# XDAmp.net
KiCad netlist of a schematic drawn in Altium Designer
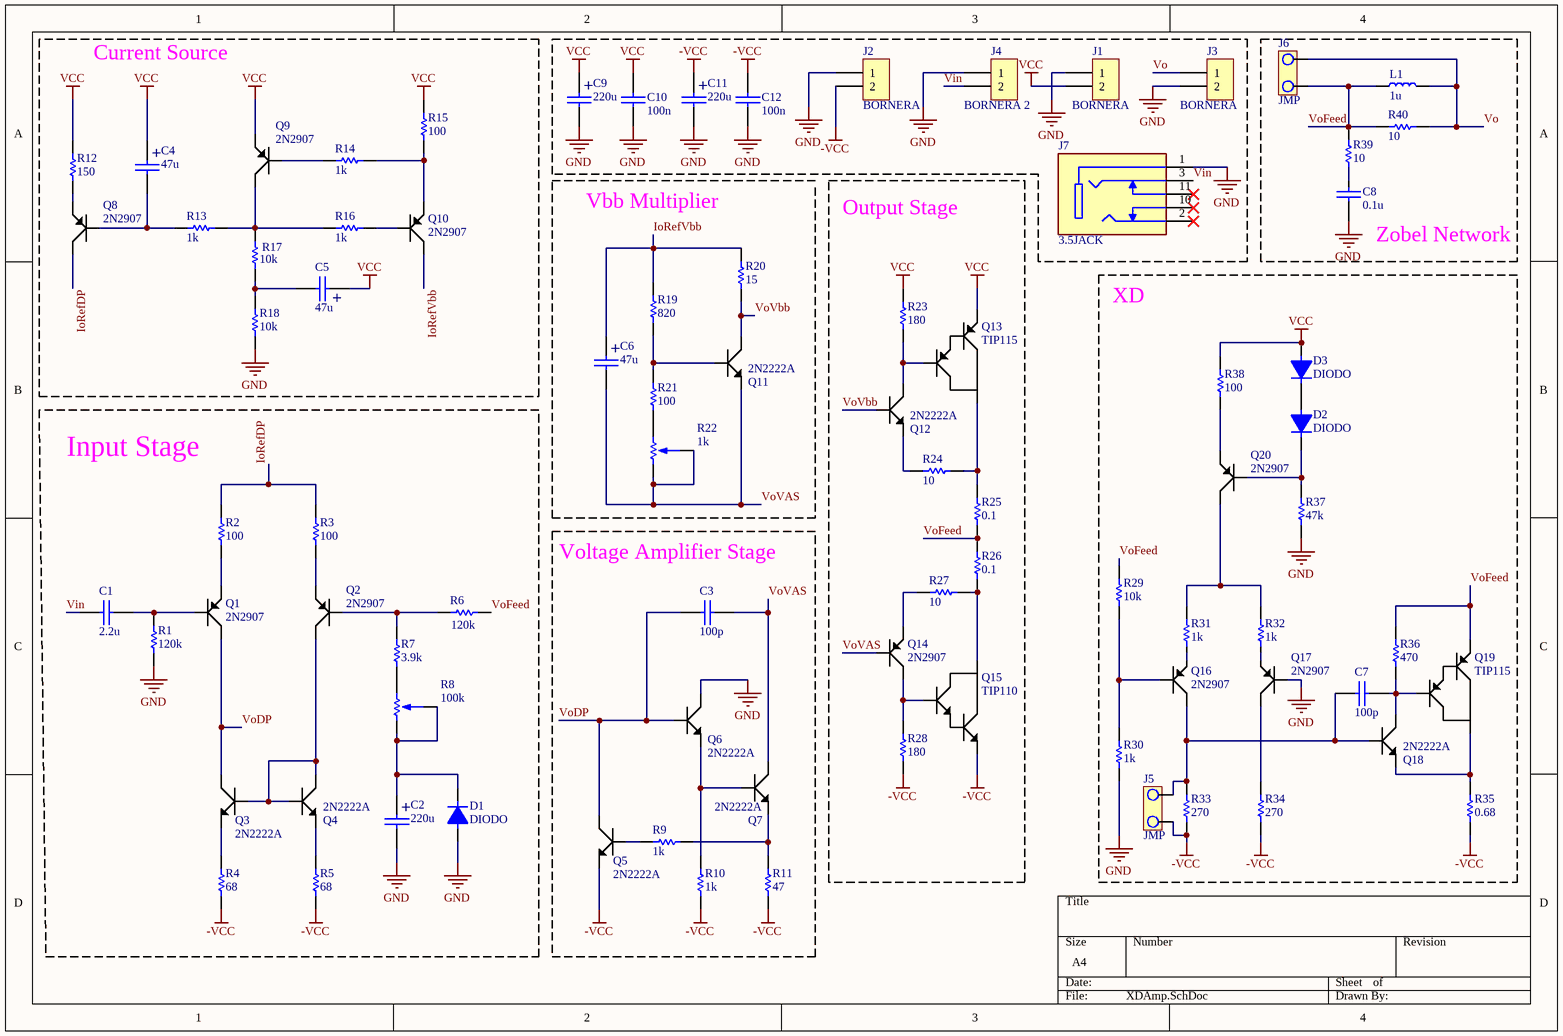
[diagram p0: XDAmp.SchDoc]

(export (version "E")
  (design (tool "Eeschema 10.0.6"))
  (components
    (comp (ref "C1")
      (value "2.2u")
      (footprint "CAP100")
      (description "Capacitor SMD 4.7nF")
      (libsource (lib "XDAmpLib") (part "CAP"))
    )
    (comp (ref "C2") (value "220u") (footprint "CAP300RP") (libsource (lib "XDAmpLib") (part "CAPPOL")))
    (comp (ref "C3")
      (value "100p")
      (footprint "0805CAP")
      (description "Capacitor SMD 4.7nF")
      (libsource (lib "XDAmpLib") (part "CAP"))
    )
    (comp (ref "C4") (value "47u") (footprint "CAP300RP") (libsource (lib "XDAmpLib") (part "CAPPOL")))
    (comp (ref "C5") (value "47u") (footprint "CAP300RP") (libsource (lib "XDAmpLib") (part "CAPPOL")))
    (comp (ref "C6") (value "47u") (footprint "CAP300RP") (libsource (lib "XDAmpLib") (part "CAPPOL")))
    (comp (ref "C7")
      (value "100p")
      (footprint "0805CAP")
      (description "Capacitor SMD 4.7nF")
      (libsource (lib "XDAmpLib") (part "CAP"))
    )
    (comp (ref "C8")
      (value "0.1u")
      (footprint "0805CAP")
      (description "Capacitor SMD 4.7nF")
      (libsource (lib "XDAmpLib") (part "CAP"))
    )
    (comp (ref "C9") (value "220u") (footprint "CAP300RP") (libsource (lib "XDAmpLib") (part "CAPPOL")))
    (comp (ref "C10")
      (value "100n")
      (footprint "0805CAP")
      (description "Capacitor SMD 4.7nF")
      (libsource (lib "XDAmpLib") (part "CAP"))
    )
    (comp (ref "C11") (value "220u") (footprint "CAP300RP") (libsource (lib "XDAmpLib") (part "CAPPOL")))
    (comp (ref "C12")
      (value "100n")
      (footprint "0805CAP")
      (description "Capacitor SMD 4.7nF")
      (libsource (lib "XDAmpLib") (part "CAP"))
    )
    (comp (ref "D1") (value "DIODO") (footprint "DO41") (libsource (lib "XDAmpLib") (part "DIODO")))
    (comp (ref "D2") (value "DIODO") (footprint "DO41") (libsource (lib "XDAmpLib") (part "DIODO")))
    (comp (ref "D3") (value "DIODO") (footprint "DO41") (libsource (lib "XDAmpLib") (part "DIODO")))
    (comp (ref "J1") (value "BORNERA") (footprint "BORNERA2") (libsource (lib "XDAmpLib") (part "BORNERA 2")))
    (comp (ref "J2") (value "BORNERA") (footprint "BORNERA2") (libsource (lib "XDAmpLib") (part "BORNERA 2")))
    (comp (ref "J3") (value "BORNERA") (footprint "BORNERA2") (libsource (lib "XDAmpLib") (part "BORNERA 2")))
    (comp (ref "J4")
      (value "BORNERA 2")
      (footprint "BORNERA2")
      (libsource (lib "XDAmpLib") (part "BORNERA 2"))
    )
    (comp (ref "J5") (value "JMP") (footprint "JUMPER2") (libsource (lib "XDAmpLib") (part "JUMPER")))
    (comp (ref "J6") (value "JMP") (footprint "JUMPER2") (libsource (lib "XDAmpLib") (part "JUMPER")))
    (comp (ref "J7")
      (value "3.5JACK")
      (footprint "3.5JACK")
      (description "3.5 mm Right-Angle Stereo Jack, 5 Pin PCB Mount, Non-Threaded")
      (fields (field (name "MP") "SJ1-3525N"))
      (libsource (lib "XDAmpLib") (part "3.5JACK"))
    )
    (comp (ref "L1") (value "1u") (footprint "RADIALIND") (libsource (lib "XDAmpLib") (part "INDUCTOR_1")))
    (comp (ref "Q1") (value "2N2907") (footprint "TO-18") (libsource (lib "XDAmpLib") (part "2N2907")))
    (comp (ref "Q2") (value "2N2907") (footprint "TO-18") (libsource (lib "XDAmpLib") (part "2N2907")))
    (comp (ref "Q3")
      (value "2N2222A")
      (footprint "TO-18")
      (fields (field (name "MANUFACTURER") "JSMSEMI"))
      (libsource (lib "XDAmpLib") (part "2N2222A"))
    )
    (comp (ref "Q4")
      (value "2N2222A")
      (footprint "TO-18")
      (fields (field (name "MANUFACTURER") "JSMSEMI"))
      (libsource (lib "XDAmpLib") (part "2N2222A"))
    )
    (comp (ref "Q5")
      (value "2N2222A")
      (footprint "TO-18")
      (fields (field (name "MANUFACTURER") "JSMSEMI"))
      (libsource (lib "XDAmpLib") (part "2N2222A"))
    )
    (comp (ref "Q6")
      (value "2N2222A")
      (footprint "TO-18")
      (fields (field (name "MANUFACTURER") "JSMSEMI"))
      (libsource (lib "XDAmpLib") (part "2N2222A"))
    )
    (comp (ref "Q7")
      (value "2N2222A")
      (footprint "TO-18")
      (fields (field (name "MANUFACTURER") "JSMSEMI"))
      (libsource (lib "XDAmpLib") (part "2N2222A"))
    )
    (comp (ref "Q8") (value "2N2907") (footprint "TO-18") (libsource (lib "XDAmpLib") (part "2N2907")))
    (comp (ref "Q9") (value "2N2907") (footprint "TO-18") (libsource (lib "XDAmpLib") (part "2N2907")))
    (comp (ref "Q10") (value "2N2907") (footprint "TO-18") (libsource (lib "XDAmpLib") (part "2N2907")))
    (comp (ref "Q11")
      (value "2N2222A")
      (footprint "TO-18")
      (fields (field (name "MANUFACTURER") "JSMSEMI"))
      (libsource (lib "XDAmpLib") (part "2N2222A"))
    )
    (comp (ref "Q12")
      (value "2N2222A")
      (footprint "TO-18")
      (fields (field (name "MANUFACTURER") "JSMSEMI"))
      (libsource (lib "XDAmpLib") (part "2N2222A"))
    )
    (comp (ref "Q13")
      (value "TIP115")
      (footprint "TO-220")
      (fields (field (name "MANUFACTURER") "JSMSEMI"))
      (libsource (lib "XDAmpLib") (part "TIP115"))
    )
    (comp (ref "Q14") (value "2N2907") (footprint "TO-18") (libsource (lib "XDAmpLib") (part "2N2907")))
    (comp (ref "Q15")
      (value "TIP110")
      (footprint "TO-220")
      (fields (field (name "MANUFACTURER") "JSMSEMI"))
      (libsource (lib "XDAmpLib") (part "TIP110"))
    )
    (comp (ref "Q16") (value "2N2907") (footprint "TO-18") (libsource (lib "XDAmpLib") (part "2N2907")))
    (comp (ref "Q17") (value "2N2907") (footprint "TO-18") (libsource (lib "XDAmpLib") (part "2N2907")))
    (comp (ref "Q18")
      (value "2N2222A")
      (footprint "TO-18")
      (fields (field (name "MANUFACTURER") "JSMSEMI"))
      (libsource (lib "XDAmpLib") (part "2N2222A"))
    )
    (comp (ref "Q19")
      (value "TIP115")
      (footprint "TO-220")
      (fields (field (name "MANUFACTURER") "JSMSEMI"))
      (libsource (lib "XDAmpLib") (part "TIP115"))
    )
    (comp (ref "Q20") (value "2N2907") (footprint "TO-18") (libsource (lib "XDAmpLib") (part "2N2907")))
    (comp (ref "R1")
      (value "120k")
      (footprint "0805")
      (description "Resistencia SMD 470ohms")
      (libsource (lib "XDAmpLib") (part "RES"))
    )
    (comp (ref "R2")
      (value "100")
      (footprint "0805")
      (description "Resistencia SMD 470ohms")
      (libsource (lib "XDAmpLib") (part "RES"))
    )
    (comp (ref "R3")
      (value "100")
      (footprint "0805")
      (description "Resistencia SMD 470ohms")
      (libsource (lib "XDAmpLib") (part "RES"))
    )
    (comp (ref "R4")
      (value "68")
      (footprint "0805")
      (description "Resistencia SMD 470ohms")
      (libsource (lib "XDAmpLib") (part "RES"))
    )
    (comp (ref "R5")
      (value "68")
      (footprint "0805")
      (description "Resistencia SMD 470ohms")
      (libsource (lib "XDAmpLib") (part "RES"))
    )
    (comp (ref "R6")
      (value "120k")
      (footprint "0805")
      (description "Resistencia SMD 470ohms")
      (libsource (lib "XDAmpLib") (part "RES"))
    )
    (comp (ref "R7")
      (value "3.9k")
      (footprint "0805")
      (description "Resistencia SMD 470ohms")
      (libsource (lib "XDAmpLib") (part "RES"))
    )
    (comp (ref "R8")
      (value "100k")
      (footprint "POTENCIOMETRO")
      (libsource (lib "XDAmpLib") (part "POTENCIOMETRO"))
    )
    (comp (ref "R9")
      (value "1k")
      (footprint "0805")
      (description "Resistencia SMD 470ohms")
      (libsource (lib "XDAmpLib") (part "RES"))
    )
    (comp (ref "R10")
      (value "1k")
      (footprint "0805")
      (description "Resistencia SMD 470ohms")
      (libsource (lib "XDAmpLib") (part "RES"))
    )
    (comp (ref "R11")
      (value "47")
      (footprint "0805")
      (description "Resistencia SMD 470ohms")
      (libsource (lib "XDAmpLib") (part "RES"))
    )
    (comp (ref "R12")
      (value "150")
      (footprint "0805")
      (description "Resistencia SMD 470ohms")
      (libsource (lib "XDAmpLib") (part "RES"))
    )
    (comp (ref "R13")
      (value "1k")
      (footprint "0805")
      (description "Resistencia SMD 470ohms")
      (libsource (lib "XDAmpLib") (part "RES"))
    )
    (comp (ref "R14")
      (value "1k")
      (footprint "0805")
      (description "Resistencia SMD 470ohms")
      (libsource (lib "XDAmpLib") (part "RES"))
    )
    (comp (ref "R15")
      (value "100")
      (footprint "0805")
      (description "Resistencia SMD 470ohms")
      (libsource (lib "XDAmpLib") (part "RES"))
    )
    (comp (ref "R16")
      (value "1k")
      (footprint "0805")
      (description "Resistencia SMD 470ohms")
      (libsource (lib "XDAmpLib") (part "RES"))
    )
    (comp (ref "R17") (value "10k") (footprint "0805") (libsource (lib "XDAmpLib") (part "RES")))
    (comp (ref "R18")
      (value "10k")
      (footprint "0805")
      (description "Resistencia SMD 470ohms")
      (libsource (lib "XDAmpLib") (part "RES"))
    )
    (comp (ref "R19")
      (value "820")
      (footprint "0805")
      (description "Resistencia SMD 470ohms")
      (libsource (lib "XDAmpLib") (part "RES"))
    )
    (comp (ref "R20")
      (value "15")
      (footprint "0805")
      (description "Resistencia SMD 470ohms")
      (libsource (lib "XDAmpLib") (part "RES"))
    )
    (comp (ref "R21")
      (value "100")
      (footprint "0805")
      (description "Resistencia SMD 470ohms")
      (libsource (lib "XDAmpLib") (part "RES"))
    )
    (comp (ref "R22") (value "1k") (footprint "PRESET V") (libsource (lib "XDAmpLib") (part "PRESET")))
    (comp (ref "R23")
      (value "180")
      (footprint "0805")
      (description "Resistencia SMD 470ohms")
      (libsource (lib "XDAmpLib") (part "RES"))
    )
    (comp (ref "R24")
      (value "10")
      (footprint "0805")
      (description "Resistencia SMD 470ohms")
      (libsource (lib "XDAmpLib") (part "RES"))
    )
    (comp (ref "R25")
      (value "0.1")
      (footprint "RES1200")
      (description "Resistencia SMD 470ohms")
      (libsource (lib "XDAmpLib") (part "RES"))
    )
    (comp (ref "R26")
      (value "0.1")
      (footprint "RES1200")
      (description "Resistencia SMD 470ohms")
      (libsource (lib "XDAmpLib") (part "RES"))
    )
    (comp (ref "R27")
      (value "10")
      (footprint "0805")
      (description "Resistencia SMD 470ohms")
      (libsource (lib "XDAmpLib") (part "RES"))
    )
    (comp (ref "R28")
      (value "180")
      (footprint "0805")
      (description "Resistencia SMD 470ohms")
      (libsource (lib "XDAmpLib") (part "RES"))
    )
    (comp (ref "R29")
      (value "10k")
      (footprint "0805")
      (description "Resistencia SMD 470ohms")
      (libsource (lib "XDAmpLib") (part "RES"))
    )
    (comp (ref "R30")
      (value "1k")
      (footprint "0805")
      (description "Resistencia SMD 470ohms")
      (libsource (lib "XDAmpLib") (part "RES"))
    )
    (comp (ref "R31")
      (value "1k")
      (footprint "0805")
      (description "Resistencia SMD 470ohms")
      (libsource (lib "XDAmpLib") (part "RES"))
    )
    (comp (ref "R32")
      (value "1k")
      (footprint "0805")
      (description "Resistencia SMD 470ohms")
      (libsource (lib "XDAmpLib") (part "RES"))
    )
    (comp (ref "R33")
      (value "270")
      (footprint "0805")
      (description "Resistencia SMD 470ohms")
      (libsource (lib "XDAmpLib") (part "RES"))
    )
    (comp (ref "R34")
      (value "270")
      (footprint "0805")
      (description "Resistencia SMD 470ohms")
      (libsource (lib "XDAmpLib") (part "RES"))
    )
    (comp (ref "R35")
      (value "0.68")
      (footprint "RES400")
      (description "Resistencia SMD 470ohms")
      (libsource (lib "XDAmpLib") (part "RES"))
    )
    (comp (ref "R36")
      (value "470")
      (footprint "0805")
      (description "Resistencia SMD 470ohms")
      (libsource (lib "XDAmpLib") (part "RES"))
    )
    (comp (ref "R37")
      (value "47k")
      (footprint "0805")
      (description "Resistencia SMD 470ohms")
      (libsource (lib "XDAmpLib") (part "RES"))
    )
    (comp (ref "R38")
      (value "100")
      (footprint "0805")
      (description "Resistencia SMD 470ohms")
      (libsource (lib "XDAmpLib") (part "RES"))
    )
    (comp (ref "R39")
      (value "10")
      (footprint "0805")
      (description "Resistencia SMD 470ohms")
      (libsource (lib "XDAmpLib") (part "RES"))
    )
    (comp (ref "R40")
      (value "10")
      (footprint "0805")
      (description "Resistencia SMD 470ohms")
      (libsource (lib "XDAmpLib") (part "RES"))
    )
  )
  (nets
    (net (code "1") (name "-VCC") (class "Default")
      (node (ref "C11") (pin "1") (pinfunction "1_1") (pintype "passive"))
      (node (ref "C12") (pin "1") (pinfunction "1_1") (pintype "passive"))
      (node (ref "J2") (pin "2") (pinfunction "2_2") (pintype "passive"))
      (node (ref "J5") (pin "2") (pinfunction "2_2") (pintype "passive"))
      (node (ref "Q15") (pin "3") (pinfunction "3_3") (pintype "passive"))
      (node (ref "Q5") (pin "1") (pinfunction "1_1") (pintype "passive"))
      (node (ref "R10") (pin "1") (pinfunction "1_1") (pintype "passive"))
      (node (ref "R11") (pin "1") (pinfunction "1_1") (pintype "passive"))
      (node (ref "R28") (pin "2") (pinfunction "2_2") (pintype "passive"))
      (node (ref "R33") (pin "1") (pinfunction "1_1") (pintype "passive"))
      (node (ref "R34") (pin "1") (pinfunction "1_1") (pintype "passive"))
      (node (ref "R35") (pin "1") (pinfunction "1_1") (pintype "passive"))
      (node (ref "R4") (pin "1") (pinfunction "1_1") (pintype "passive"))
      (node (ref "R5") (pin "1") (pinfunction "1_1") (pintype "passive"))
    )
    (net (code "2") (name "/IoRefDP") (class "Default")
      (node (ref "Q8") (pin "3") (pinfunction "3_3") (pintype "passive"))
      (node (ref "R2") (pin "2") (pinfunction "2_2") (pintype "passive"))
      (node (ref "R3") (pin "2") (pinfunction "2_2") (pintype "passive"))
    )
    (net (code "3") (name "/IoRefVbb") (class "Default")
      (node (ref "C6") (pin "1") (pinfunction "1_1") (pintype "passive"))
      (node (ref "Q10") (pin "3") (pinfunction "3_3") (pintype "passive"))
      (node (ref "R19") (pin "1") (pinfunction "1_1") (pintype "passive"))
      (node (ref "R20") (pin "1") (pinfunction "1_1") (pintype "passive"))
    )
    (net (code "4") (name "/Vin") (class "Default")
      (node (ref "C1") (pin "1") (pinfunction "1_1") (pintype "passive"))
      (node (ref "J4") (pin "2") (pinfunction "2_2") (pintype "passive"))
      (node (ref "J7") (pin "3") (pinfunction "3_3") (pintype "passive"))
    )
    (net (code "5") (name "/Vo") (class "Default")
      (node (ref "J3") (pin "1") (pinfunction "1_1") (pintype "passive"))
      (node (ref "J6") (pin "1") (pinfunction "1_1") (pintype "passive"))
      (node (ref "L1") (pin "2") (pinfunction "2_2") (pintype "passive"))
      (node (ref "R40") (pin "1") (pinfunction "1_1") (pintype "passive"))
    )
    (net (code "6") (name "/VoDP") (class "Default")
      (node (ref "C3") (pin "2") (pinfunction "2_2") (pintype "passive"))
      (node (ref "Q1") (pin "3") (pinfunction "3_3") (pintype "passive"))
      (node (ref "Q3") (pin "3") (pinfunction "3_3") (pintype "passive"))
      (node (ref "Q5") (pin "3") (pinfunction "3_3") (pintype "passive"))
      (node (ref "Q6") (pin "2") (pinfunction "2_2") (pintype "passive"))
    )
    (net (code "7") (name "/VoFeed") (class "Default")
      (node (ref "J6") (pin "2") (pinfunction "2_2") (pintype "passive"))
      (node (ref "L1") (pin "1") (pinfunction "1_1") (pintype "passive"))
      (node (ref "Q19") (pin "3") (pinfunction "3_3") (pintype "passive"))
      (node (ref "R25") (pin "1") (pinfunction "1_1") (pintype "passive"))
      (node (ref "R26") (pin "2") (pinfunction "2_2") (pintype "passive"))
      (node (ref "R29") (pin "2") (pinfunction "2_2") (pintype "passive"))
      (node (ref "R36") (pin "2") (pinfunction "2_2") (pintype "passive"))
      (node (ref "R39") (pin "1") (pinfunction "1_1") (pintype "passive"))
      (node (ref "R40") (pin "2") (pinfunction "2_2") (pintype "passive"))
      (node (ref "R6") (pin "1") (pinfunction "1_1") (pintype "passive"))
    )
    (net (code "8") (name "/VoVAS") (class "Default")
      (node (ref "C3") (pin "1") (pinfunction "1_1") (pintype "passive"))
      (node (ref "C6") (pin "2") (pinfunction "2_2") (pintype "passive"))
      (node (ref "Q11") (pin "1") (pinfunction "1_1") (pintype "passive"))
      (node (ref "Q14") (pin "2") (pinfunction "2_2") (pintype "passive"))
      (node (ref "Q7") (pin "3") (pinfunction "3_3") (pintype "passive"))
      (node (ref "R22") (pin "2") (pinfunction "2_2") (pintype "passive"))
      (node (ref "R22") (pin "3") (pinfunction "3_3") (pintype "passive"))
    )
    (net (code "9") (name "/VoVbb") (class "Default")
      (node (ref "Q11") (pin "3") (pinfunction "3_3") (pintype "passive"))
      (node (ref "Q12") (pin "2") (pinfunction "2_2") (pintype "passive"))
      (node (ref "R20") (pin "2") (pinfunction "2_2") (pintype "passive"))
    )
    (net (code "10") (name "GND") (class "Default")
      (node (ref "C10") (pin "2") (pinfunction "2_2") (pintype "passive"))
      (node (ref "C11") (pin "2") (pinfunction "2_2") (pintype "passive"))
      (node (ref "C12") (pin "2") (pinfunction "2_2") (pintype "passive"))
      (node (ref "C2") (pin "2") (pinfunction "2_2") (pintype "passive"))
      (node (ref "C8") (pin "1") (pinfunction "1_1") (pintype "passive"))
      (node (ref "C9") (pin "2") (pinfunction "2_2") (pintype "passive"))
      (node (ref "D1") (pin "1") (pinfunction "1_1") (pintype "passive"))
      (node (ref "J1") (pin "1") (pinfunction "1_1") (pintype "passive"))
      (node (ref "J2") (pin "1") (pinfunction "1_1") (pintype "passive"))
      (node (ref "J3") (pin "2") (pinfunction "2_2") (pintype "passive"))
      (node (ref "J4") (pin "1") (pinfunction "1_1") (pintype "passive"))
      (node (ref "J7") (pin "1") (pinfunction "1_1") (pintype "passive"))
      (node (ref "Q17") (pin "2") (pinfunction "2_2") (pintype "passive"))
      (node (ref "Q6") (pin "3") (pinfunction "3_3") (pintype "passive"))
      (node (ref "R1") (pin "1") (pinfunction "1_1") (pintype "passive"))
      (node (ref "R18") (pin "2") (pinfunction "2_2") (pintype "passive"))
      (node (ref "R30") (pin "1") (pinfunction "1_1") (pintype "passive"))
      (node (ref "R37") (pin "1") (pinfunction "1_1") (pintype "passive"))
    )
    (net (code "11") (name "Net-(C1-Pad2)") (class "Default")
      (node (ref "C1") (pin "2") (pinfunction "2_2") (pintype "passive"))
      (node (ref "Q1") (pin "2") (pinfunction "2_2") (pintype "passive"))
      (node (ref "R1") (pin "2") (pinfunction "2_2") (pintype "passive"))
    )
    (net (code "12") (name "Net-(C2-Pad1)") (class "Default")
      (node (ref "C2") (pin "1") (pinfunction "1_1") (pintype "passive"))
      (node (ref "D1") (pin "2") (pinfunction "2_2") (pintype "passive"))
      (node (ref "R8") (pin "2") (pinfunction "2_2") (pintype "passive"))
      (node (ref "R8") (pin "3") (pinfunction "3_3") (pintype "passive"))
    )
    (net (code "13") (name "Net-(C4-Pad2)") (class "Default")
      (node (ref "C4") (pin "2") (pinfunction "2_2") (pintype "passive"))
      (node (ref "Q8") (pin "2") (pinfunction "2_2") (pintype "passive"))
      (node (ref "R13") (pin "2") (pinfunction "2_2") (pintype "passive"))
    )
    (net (code "14") (name "Net-(C5-Pad2)") (class "Default")
      (node (ref "C5") (pin "2") (pinfunction "2_2") (pintype "passive"))
      (node (ref "R17") (pin "2") (pinfunction "2_2") (pintype "passive"))
      (node (ref "R18") (pin "1") (pinfunction "1_1") (pintype "passive"))
    )
    (net (code "15") (name "Net-(C7-Pad1)") (class "Default")
      (node (ref "C7") (pin "1") (pinfunction "1_1") (pintype "passive"))
      (node (ref "J5") (pin "1") (pinfunction "1_1") (pintype "passive"))
      (node (ref "Q16") (pin "3") (pinfunction "3_3") (pintype "passive"))
      (node (ref "Q18") (pin "2") (pinfunction "2_2") (pintype "passive"))
      (node (ref "R33") (pin "2") (pinfunction "2_2") (pintype "passive"))
    )
    (net (code "16") (name "Net-(C7-Pad2)") (class "Default")
      (node (ref "C7") (pin "2") (pinfunction "2_2") (pintype "passive"))
      (node (ref "Q18") (pin "3") (pinfunction "3_3") (pintype "passive"))
      (node (ref "Q19") (pin "1") (pinfunction "1_1") (pintype "passive"))
      (node (ref "R36") (pin "1") (pinfunction "1_1") (pintype "passive"))
    )
    (net (code "17") (name "Net-(C8-Pad2)") (class "Default")
      (node (ref "C8") (pin "2") (pinfunction "2_2") (pintype "passive"))
      (node (ref "R39") (pin "2") (pinfunction "2_2") (pintype "passive"))
    )
    (net (code "18") (name "Net-(D2-Pad1)") (class "Default")
      (node (ref "D2") (pin "1") (pinfunction "1_1") (pintype "passive"))
      (node (ref "D3") (pin "2") (pinfunction "2_2") (pintype "passive"))
    )
    (net (code "19") (name "Net-(D2-Pad2)") (class "Default")
      (node (ref "D2") (pin "2") (pinfunction "2_2") (pintype "passive"))
      (node (ref "Q20") (pin "2") (pinfunction "2_2") (pintype "passive"))
      (node (ref "R37") (pin "2") (pinfunction "2_2") (pintype "passive"))
    )
    (net (code "20") (name "Net-(Q1-Pad1)") (class "Default")
      (node (ref "Q1") (pin "1") (pinfunction "1_1") (pintype "passive"))
      (node (ref "R2") (pin "1") (pinfunction "1_1") (pintype "passive"))
    )
    (net (code "21") (name "Net-(Q2-Pad1)") (class "Default")
      (node (ref "Q2") (pin "1") (pinfunction "1_1") (pintype "passive"))
      (node (ref "R3") (pin "1") (pinfunction "1_1") (pintype "passive"))
    )
    (net (code "22") (name "Net-(Q2-Pad2)") (class "Default")
      (node (ref "Q2") (pin "2") (pinfunction "2_2") (pintype "passive"))
      (node (ref "R6") (pin "2") (pinfunction "2_2") (pintype "passive"))
      (node (ref "R7") (pin "1") (pinfunction "1_1") (pintype "passive"))
    )
    (net (code "23") (name "Net-(Q2-Pad3)") (class "Default")
      (node (ref "Q2") (pin "3") (pinfunction "3_3") (pintype "passive"))
      (node (ref "Q3") (pin "2") (pinfunction "2_2") (pintype "passive"))
      (node (ref "Q4") (pin "2") (pinfunction "2_2") (pintype "passive"))
      (node (ref "Q4") (pin "3") (pinfunction "3_3") (pintype "passive"))
    )
    (net (code "24") (name "Net-(Q3-Pad1)") (class "Default")
      (node (ref "Q3") (pin "1") (pinfunction "1_1") (pintype "passive"))
      (node (ref "R4") (pin "2") (pinfunction "2_2") (pintype "passive"))
    )
    (net (code "25") (name "Net-(Q4-Pad1)") (class "Default")
      (node (ref "Q4") (pin "1") (pinfunction "1_1") (pintype "passive"))
      (node (ref "R5") (pin "2") (pinfunction "2_2") (pintype "passive"))
    )
    (net (code "26") (name "Net-(Q5-Pad2)") (class "Default")
      (node (ref "Q5") (pin "2") (pinfunction "2_2") (pintype "passive"))
      (node (ref "R9") (pin "2") (pinfunction "2_2") (pintype "passive"))
    )
    (net (code "27") (name "Net-(Q6-Pad1)") (class "Default")
      (node (ref "Q6") (pin "1") (pinfunction "1_1") (pintype "passive"))
      (node (ref "Q7") (pin "2") (pinfunction "2_2") (pintype "passive"))
      (node (ref "R10") (pin "2") (pinfunction "2_2") (pintype "passive"))
    )
    (net (code "28") (name "Net-(Q7-Pad1)") (class "Default")
      (node (ref "Q7") (pin "1") (pinfunction "1_1") (pintype "passive"))
      (node (ref "R11") (pin "2") (pinfunction "2_2") (pintype "passive"))
      (node (ref "R9") (pin "1") (pinfunction "1_1") (pintype "passive"))
    )
    (net (code "29") (name "Net-(Q8-Pad1)") (class "Default")
      (node (ref "Q8") (pin "1") (pinfunction "1_1") (pintype "passive"))
      (node (ref "R12") (pin "1") (pinfunction "1_1") (pintype "passive"))
    )
    (net (code "30") (name "Net-(Q9-Pad2)") (class "Default")
      (node (ref "Q9") (pin "2") (pinfunction "2_2") (pintype "passive"))
      (node (ref "R14") (pin "2") (pinfunction "2_2") (pintype "passive"))
    )
    (net (code "31") (name "Net-(Q9-Pad3)") (class "Default")
      (node (ref "Q9") (pin "3") (pinfunction "3_3") (pintype "passive"))
      (node (ref "R13") (pin "1") (pinfunction "1_1") (pintype "passive"))
      (node (ref "R16") (pin "2") (pinfunction "2_2") (pintype "passive"))
      (node (ref "R17") (pin "1") (pinfunction "1_1") (pintype "passive"))
    )
    (net (code "32") (name "Net-(Q10-Pad1)") (class "Default")
      (node (ref "Q10") (pin "1") (pinfunction "1_1") (pintype "passive"))
      (node (ref "R14") (pin "1") (pinfunction "1_1") (pintype "passive"))
      (node (ref "R15") (pin "2") (pinfunction "2_2") (pintype "passive"))
    )
    (net (code "33") (name "Net-(Q10-Pad2)") (class "Default")
      (node (ref "Q10") (pin "2") (pinfunction "2_2") (pintype "passive"))
      (node (ref "R16") (pin "1") (pinfunction "1_1") (pintype "passive"))
    )
    (net (code "34") (name "Net-(Q11-Pad2)") (class "Default")
      (node (ref "Q11") (pin "2") (pinfunction "2_2") (pintype "passive"))
      (node (ref "R19") (pin "2") (pinfunction "2_2") (pintype "passive"))
      (node (ref "R21") (pin "1") (pinfunction "1_1") (pintype "passive"))
    )
    (net (code "35") (name "Net-(Q12-Pad1)") (class "Default")
      (node (ref "Q12") (pin "1") (pinfunction "1_1") (pintype "passive"))
      (node (ref "R24") (pin "1") (pinfunction "1_1") (pintype "passive"))
    )
    (net (code "36") (name "Net-(Q12-Pad3)") (class "Default")
      (node (ref "Q12") (pin "3") (pinfunction "3_3") (pintype "passive"))
      (node (ref "Q13") (pin "1") (pinfunction "1_1") (pintype "passive"))
      (node (ref "R23") (pin "2") (pinfunction "2_2") (pintype "passive"))
    )
    (net (code "37") (name "Net-(Q13-Pad2)") (class "Default")
      (node (ref "Q13") (pin "2") (pinfunction "2_2") (pintype "passive"))
      (node (ref "R24") (pin "2") (pinfunction "2_2") (pintype "passive"))
      (node (ref "R25") (pin "2") (pinfunction "2_2") (pintype "passive"))
    )
    (net (code "38") (name "Net-(Q14-Pad1)") (class "Default")
      (node (ref "Q14") (pin "1") (pinfunction "1_1") (pintype "passive"))
      (node (ref "R27") (pin "1") (pinfunction "1_1") (pintype "passive"))
    )
    (net (code "39") (name "Net-(Q14-Pad3)") (class "Default")
      (node (ref "Q14") (pin "3") (pinfunction "3_3") (pintype "passive"))
      (node (ref "Q15") (pin "1") (pinfunction "1_1") (pintype "passive"))
      (node (ref "R28") (pin "1") (pinfunction "1_1") (pintype "passive"))
    )
    (net (code "40") (name "Net-(Q15-Pad2)") (class "Default")
      (node (ref "Q15") (pin "2") (pinfunction "2_2") (pintype "passive"))
      (node (ref "R26") (pin "1") (pinfunction "1_1") (pintype "passive"))
      (node (ref "R27") (pin "2") (pinfunction "2_2") (pintype "passive"))
    )
    (net (code "41") (name "Net-(Q16-Pad1)") (class "Default")
      (node (ref "Q16") (pin "1") (pinfunction "1_1") (pintype "passive"))
      (node (ref "R31") (pin "1") (pinfunction "1_1") (pintype "passive"))
    )
    (net (code "42") (name "Net-(Q16-Pad2)") (class "Default")
      (node (ref "Q16") (pin "2") (pinfunction "2_2") (pintype "passive"))
      (node (ref "R29") (pin "1") (pinfunction "1_1") (pintype "passive"))
      (node (ref "R30") (pin "2") (pinfunction "2_2") (pintype "passive"))
    )
    (net (code "43") (name "Net-(Q17-Pad1)") (class "Default")
      (node (ref "Q17") (pin "1") (pinfunction "1_1") (pintype "passive"))
      (node (ref "R32") (pin "1") (pinfunction "1_1") (pintype "passive"))
    )
    (net (code "44") (name "Net-(Q17-Pad3)") (class "Default")
      (node (ref "Q17") (pin "3") (pinfunction "3_3") (pintype "passive"))
      (node (ref "R34") (pin "2") (pinfunction "2_2") (pintype "passive"))
    )
    (net (code "45") (name "Net-(Q18-Pad1)") (class "Default")
      (node (ref "Q18") (pin "1") (pinfunction "1_1") (pintype "passive"))
      (node (ref "Q19") (pin "2") (pinfunction "2_2") (pintype "passive"))
      (node (ref "R35") (pin "2") (pinfunction "2_2") (pintype "passive"))
    )
    (net (code "46") (name "Net-(Q20-Pad1)") (class "Default")
      (node (ref "Q20") (pin "1") (pinfunction "1_1") (pintype "passive"))
      (node (ref "R38") (pin "1") (pinfunction "1_1") (pintype "passive"))
    )
    (net (code "47") (name "Net-(Q20-Pad3)") (class "Default")
      (node (ref "Q20") (pin "3") (pinfunction "3_3") (pintype "passive"))
      (node (ref "R31") (pin "2") (pinfunction "2_2") (pintype "passive"))
      (node (ref "R32") (pin "2") (pinfunction "2_2") (pintype "passive"))
    )
    (net (code "48") (name "Net-(R7-Pad2)") (class "Default")
      (node (ref "R7") (pin "2") (pinfunction "2_2") (pintype "passive"))
      (node (ref "R8") (pin "1") (pinfunction "1_1") (pintype "passive"))
    )
    (net (code "49") (name "Net-(R21-Pad2)") (class "Default")
      (node (ref "R21") (pin "2") (pinfunction "2_2") (pintype "passive"))
      (node (ref "R22") (pin "1") (pinfunction "1_1") (pintype "passive"))
    )
    (net (code "50") (name "VCC") (class "Default")
      (node (ref "C10") (pin "1") (pinfunction "1_1") (pintype "passive"))
      (node (ref "C4") (pin "1") (pinfunction "1_1") (pintype "passive"))
      (node (ref "C5") (pin "1") (pinfunction "1_1") (pintype "passive"))
      (node (ref "C9") (pin "1") (pinfunction "1_1") (pintype "passive"))
      (node (ref "D3") (pin "1") (pinfunction "1_1") (pintype "passive"))
      (node (ref "J1") (pin "2") (pinfunction "2_2") (pintype "passive"))
      (node (ref "Q13") (pin "3") (pinfunction "3_3") (pintype "passive"))
      (node (ref "Q9") (pin "1") (pinfunction "1_1") (pintype "passive"))
      (node (ref "R12") (pin "2") (pinfunction "2_2") (pintype "passive"))
      (node (ref "R15") (pin "1") (pinfunction "1_1") (pintype "passive"))
      (node (ref "R23") (pin "1") (pinfunction "1_1") (pintype "passive"))
      (node (ref "R38") (pin "2") (pinfunction "2_2") (pintype "passive"))
    )
    (net (code "51") (name "unconnected-(J7-Pad2)") (class "Default")
      (node (ref "J7") (pin "2") (pinfunction "2_2") (pintype "passive+no_connect"))
    )
    (net (code "52") (name "unconnected-(J7-Pad10)") (class "Default")
      (node (ref "J7") (pin "10") (pinfunction "10_10") (pintype "passive+no_connect"))
    )
    (net (code "53") (name "unconnected-(J7-Pad11)") (class "Default")
      (node (ref "J7") (pin "11") (pinfunction "11_11") (pintype "passive+no_connect"))
    )
  )
)
